# M5_Shield_RS485_V1_1.net
KiCad netlist of a schematic drawn in EAGLE
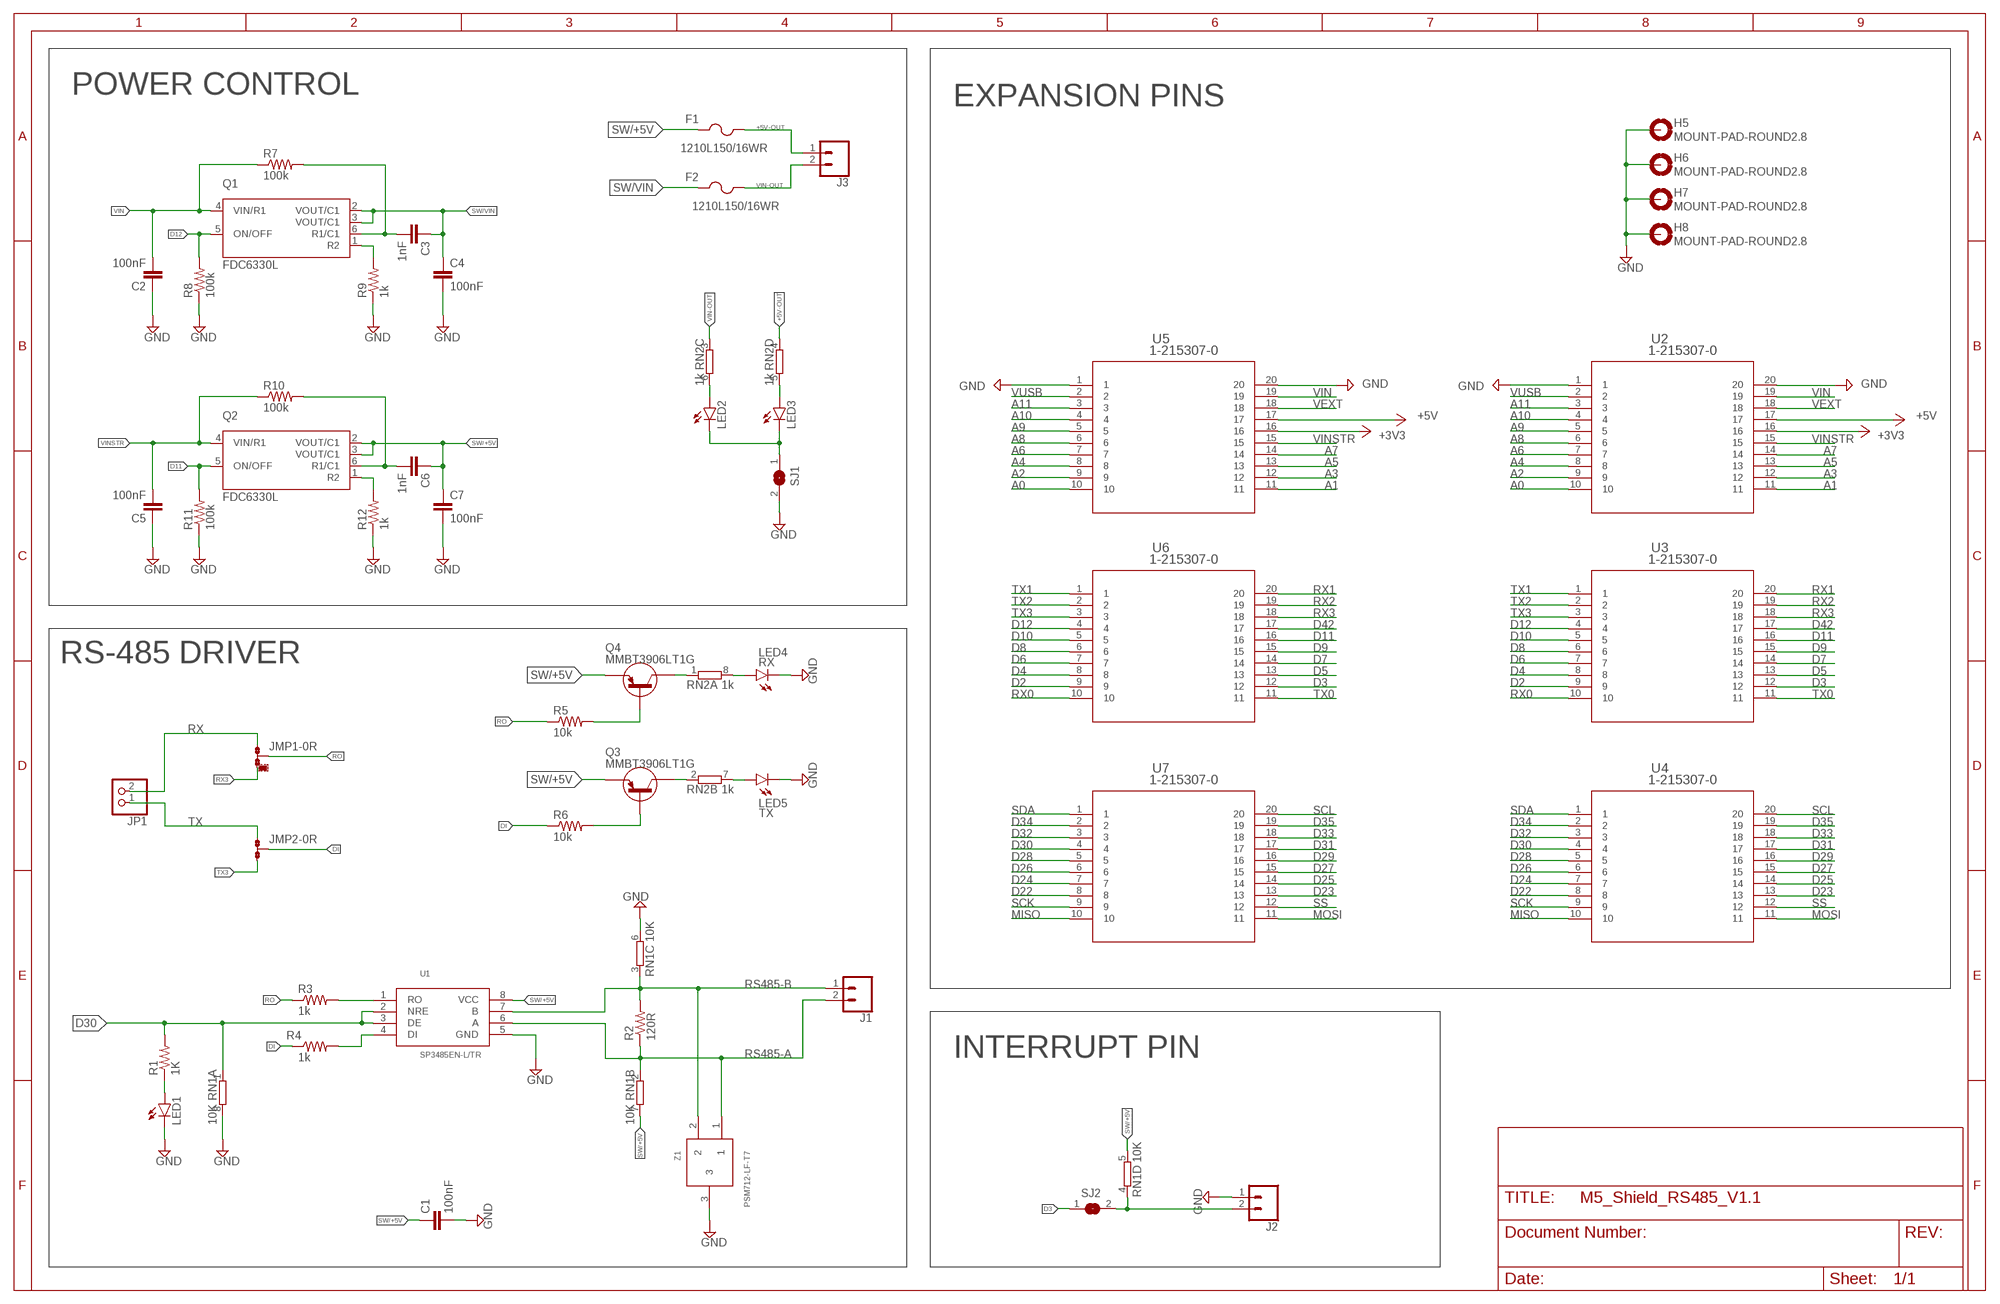
[diagram p0: schematic, sheet 1]

(export (version "E")
  (design (tool "Eeschema 10.0.6"))
  (components
    (comp (ref "C1")
      (value "100nF")
      (footprint "eagle-import:C0603K")
      (libsource (lib "eagle-import") (part "C-EUC0603K"))
    )
    (comp (ref "C2")
      (value "100nF")
      (footprint "eagle-import:C0603")
      (libsource (lib "eagle-import") (part "C-EUC0603"))
    )
    (comp (ref "C3")
      (value "1nF")
      (footprint "eagle-import:C0603")
      (libsource (lib "eagle-import") (part "C-EUC0603"))
    )
    (comp (ref "C4")
      (value "100nF")
      (footprint "eagle-import:C0603")
      (libsource (lib "eagle-import") (part "C-EUC0603"))
    )
    (comp (ref "C5")
      (value "100nF")
      (footprint "eagle-import:C0603")
      (libsource (lib "eagle-import") (part "C-EUC0603"))
    )
    (comp (ref "C6")
      (value "1nF")
      (footprint "eagle-import:C0603")
      (libsource (lib "eagle-import") (part "C-EUC0603"))
    )
    (comp (ref "C7")
      (value "100nF")
      (footprint "eagle-import:C0603")
      (libsource (lib "eagle-import") (part "C-EUC0603"))
    )
    (comp (ref "F1")
      (value "1210L150/16WR")
      (footprint "eagle-import:1210LSERIES")
      (libsource (lib "eagle-import") (part "1210L150/16WR"))
    )
    (comp (ref "F2")
      (value "1210L150/16WR")
      (footprint "eagle-import:1210LSERIES")
      (libsource (lib "eagle-import") (part "1210L150/16WR"))
    )
    (comp (ref "H5")
      (value "MOUNT-PAD-ROUND2.8")
      (footprint "eagle-import:2,8-PAD")
      (libsource (lib "eagle-import") (part "MOUNT-PAD-ROUND2.8"))
    )
    (comp (ref "H6")
      (value "MOUNT-PAD-ROUND2.8")
      (footprint "eagle-import:2,8-PAD")
      (libsource (lib "eagle-import") (part "MOUNT-PAD-ROUND2.8"))
    )
    (comp (ref "H7")
      (value "MOUNT-PAD-ROUND2.8")
      (footprint "eagle-import:2,8-PAD")
      (libsource (lib "eagle-import") (part "MOUNT-PAD-ROUND2.8"))
    )
    (comp (ref "H8")
      (value "MOUNT-PAD-ROUND2.8")
      (footprint "eagle-import:2,8-PAD")
      (libsource (lib "eagle-import") (part "MOUNT-PAD-ROUND2.8"))
    )
    (comp (ref "J1")
      (value "CONN_023.5MM")
      (footprint "eagle-import:SCREWTERMINAL-3.5MM-2")
      (libsource (lib "eagle-import") (part "CONN_023.5MM"))
    )
    (comp (ref "J2")
      (value "CONN_023.5MM")
      (footprint "eagle-import:SCREWTERMINAL-3.5MM-2")
      (libsource (lib "eagle-import") (part "CONN_023.5MM"))
    )
    (comp (ref "J3")
      (value "CONN_023.5MM")
      (footprint "eagle-import:SCREWTERMINAL-3.5MM-2")
      (libsource (lib "eagle-import") (part "CONN_023.5MM"))
    )
    (comp (ref "JMP1")
      (value "0R-JUMPA")
      (footprint "eagle-import:A0R-JMP")
      (libsource (lib "eagle-import") (part "0R-JUMPA"))
    )
    (comp (ref "JMP2")
      (value "0R-JUMPA")
      (footprint "eagle-import:A0R-JMP")
      (libsource (lib "eagle-import") (part "0R-JUMPA"))
    )
    (comp (ref "JP1")
      (value "PINHD-1X2")
      (footprint "eagle-import:1X02")
      (libsource (lib "eagle-import") (part "PINHD-1X2"))
    )
    (comp (ref "LED1")
      (value "LEDCHIPLED_0603")
      (footprint "eagle-import:CHIPLED_0603")
      (libsource (lib "eagle-import") (part "LEDCHIPLED_0603"))
    )
    (comp (ref "LED2")
      (value "LEDCHIP-LED0603")
      (footprint "eagle-import:CHIP-LED0603")
      (libsource (lib "eagle-import") (part "LEDCHIP-LED0603"))
    )
    (comp (ref "LED3")
      (value "LEDCHIP-LED0603")
      (footprint "eagle-import:CHIP-LED0603")
      (libsource (lib "eagle-import") (part "LEDCHIP-LED0603"))
    )
    (comp (ref "LED4")
      (value "RX")
      (footprint "eagle-import:CHIP-LED0603")
      (libsource (lib "eagle-import") (part "LEDCHIP-LED0603"))
    )
    (comp (ref "LED5")
      (value "TX")
      (footprint "eagle-import:CHIP-LED0603")
      (libsource (lib "eagle-import") (part "LEDCHIP-LED0603"))
    )
    (comp (ref "Q1")
      (value "FDC6330L")
      (footprint "eagle-import:SOT95P280X110-6N")
      (fields (field (name "DIGI-KEY_PART_NUMBER") "FDC6330LCT-ND") (field (name "MF") "ON Semiconductor"))
      (libsource (lib "eagle-import") (part "FDC6330L"))
    )
    (comp (ref "Q2")
      (value "FDC6330L")
      (footprint "eagle-import:SOT95P280X110-6N")
      (fields (field (name "DIGI-KEY_PART_NUMBER") "FDC6330LCT-ND") (field (name "MF") "ON Semiconductor"))
      (libsource (lib "eagle-import") (part "FDC6330L"))
    )
    (comp (ref "Q3")
      (value "MMBT3906LT1G")
      (footprint "eagle-import:SOT23")
      (fields (field (name "MF") "ON Semiconductor"))
      (libsource (lib "eagle-import") (part "MMBT3906LT1G"))
    )
    (comp (ref "Q4")
      (value "MMBT3906LT1G")
      (footprint "eagle-import:SOT23")
      (fields (field (name "MF") "ON Semiconductor"))
      (libsource (lib "eagle-import") (part "MMBT3906LT1G"))
    )
    (comp (ref "R1")
      (value "1K")
      (footprint "eagle-import:R0603")
      (libsource (lib "eagle-import") (part "R-US_R0603"))
    )
    (comp (ref "R2")
      (value "120R")
      (footprint "eagle-import:R0603")
      (libsource (lib "eagle-import") (part "R-US_R0603"))
    )
    (comp (ref "R3")
      (value "1k")
      (footprint "eagle-import:R0603")
      (libsource (lib "eagle-import") (part "R-US_R0603"))
    )
    (comp (ref "R4")
      (value "1k")
      (footprint "eagle-import:R0603")
      (libsource (lib "eagle-import") (part "R-US_R0603"))
    )
    (comp (ref "R5")
      (value "10k")
      (footprint "eagle-import:R0603")
      (libsource (lib "eagle-import") (part "R-US_R0603"))
    )
    (comp (ref "R6")
      (value "10k")
      (footprint "eagle-import:R0603")
      (libsource (lib "eagle-import") (part "R-US_R0603"))
    )
    (comp (ref "R7")
      (value "100k")
      (footprint "eagle-import:R0603")
      (libsource (lib "eagle-import") (part "R-US_R0603"))
    )
    (comp (ref "R8")
      (value "100k")
      (footprint "eagle-import:R0603")
      (libsource (lib "eagle-import") (part "R-US_R0603"))
    )
    (comp (ref "R9")
      (value "1k")
      (footprint "eagle-import:R0603")
      (libsource (lib "eagle-import") (part "R-US_R0603"))
    )
    (comp (ref "R10")
      (value "100k")
      (footprint "eagle-import:R0603")
      (libsource (lib "eagle-import") (part "R-US_R0603"))
    )
    (comp (ref "R11")
      (value "100k")
      (footprint "eagle-import:R0603")
      (libsource (lib "eagle-import") (part "R-US_R0603"))
    )
    (comp (ref "R12")
      (value "1k")
      (footprint "eagle-import:R0603")
      (libsource (lib "eagle-import") (part "R-US_R0603"))
    )
    (comp (ref "RN1")
      (value "10K")
      (footprint "eagle-import:0603-ARV")
      (libsource (lib "eagle-import") (part "4R-N0603-ARV"))
    )
    (comp (ref "RN2")
      (value "1k")
      (footprint "eagle-import:0603-ARV")
      (libsource (lib "eagle-import") (part "4R-N0603-ARV"))
    )
    (comp (ref "SJ1") (value "SJ") (footprint "eagle-import:SJ") (libsource (lib "eagle-import") (part "SJ")))
    (comp (ref "SJ2") (value "SJ") (footprint "eagle-import:SJ") (libsource (lib "eagle-import") (part "SJ")))
    (comp (ref "U1")
      (value "SP3485EN-L/TR")
      (footprint "eagle-import:SP3485EN-L_TR")
      (libsource (lib "eagle-import") (part "SP3485EN-L/TR"))
    )
    (comp (ref "U2")
      (value "1-215307-0")
      (footprint "eagle-import:1-215307-0")
      (libsource (lib "eagle-import") (part "1-215307-0"))
    )
    (comp (ref "U3")
      (value "1-215307-0")
      (footprint "eagle-import:1-215307-0")
      (libsource (lib "eagle-import") (part "1-215307-0"))
    )
    (comp (ref "U4")
      (value "1-215307-0")
      (footprint "eagle-import:1-215307-0")
      (libsource (lib "eagle-import") (part "1-215307-0"))
    )
    (comp (ref "U5")
      (value "1-215307-0")
      (footprint "eagle-import:1-215307-0")
      (libsource (lib "eagle-import") (part "1-215307-0"))
    )
    (comp (ref "U6")
      (value "1-215307-0")
      (footprint "eagle-import:1-215307-0")
      (libsource (lib "eagle-import") (part "1-215307-0"))
    )
    (comp (ref "U7")
      (value "1-215307-0")
      (footprint "eagle-import:1-215307-0")
      (libsource (lib "eagle-import") (part "1-215307-0"))
    )
    (comp (ref "Z1")
      (value "PSM712-LF-T7")
      (footprint "eagle-import:SOT23")
      (libsource (lib "eagle-import") (part "PSM712-LF-T7"))
    )
  )
  (nets
    (net (code "1") (name "+3V3") (class "Default")
      (node (ref "U2") (pin "16") (pinfunction "16_16") (pintype "passive"))
      (node (ref "U5") (pin "16") (pinfunction "16_16") (pintype "passive"))
    )
    (net (code "2") (name "+5V") (class "Default")
      (node (ref "U2") (pin "17") (pinfunction "17_17") (pintype "passive"))
      (node (ref "U5") (pin "17") (pinfunction "17_17") (pintype "passive"))
    )
    (net (code "3") (name "+5V-OUT") (class "Default")
      (node (ref "F1") (pin "2") (pinfunction "2_2") (pintype "passive"))
      (node (ref "J3") (pin "1") (pinfunction "1_1") (pintype "passive"))
      (node (ref "RN2") (pin "4") (pinfunction "1_4") (pintype "passive"))
    )
    (net (code "4") (name "/A0") (class "Default")
      (node (ref "U2") (pin "10") (pinfunction "10_10") (pintype "passive"))
      (node (ref "U5") (pin "10") (pinfunction "10_10") (pintype "passive"))
    )
    (net (code "5") (name "/A1") (class "Default")
      (node (ref "U2") (pin "11") (pinfunction "11_11") (pintype "passive"))
      (node (ref "U5") (pin "11") (pinfunction "11_11") (pintype "passive"))
    )
    (net (code "6") (name "/A2") (class "Default")
      (node (ref "U2") (pin "9") (pinfunction "9_9") (pintype "passive"))
      (node (ref "U5") (pin "9") (pinfunction "9_9") (pintype "passive"))
    )
    (net (code "7") (name "/A3") (class "Default")
      (node (ref "U2") (pin "12") (pinfunction "12_12") (pintype "passive"))
      (node (ref "U5") (pin "12") (pinfunction "12_12") (pintype "passive"))
    )
    (net (code "8") (name "/A4") (class "Default")
      (node (ref "U2") (pin "8") (pinfunction "8_8") (pintype "passive"))
      (node (ref "U5") (pin "8") (pinfunction "8_8") (pintype "passive"))
    )
    (net (code "9") (name "/A5") (class "Default")
      (node (ref "U2") (pin "13") (pinfunction "13_13") (pintype "passive"))
      (node (ref "U5") (pin "13") (pinfunction "13_13") (pintype "passive"))
    )
    (net (code "10") (name "/A6") (class "Default")
      (node (ref "U2") (pin "7") (pinfunction "7_7") (pintype "passive"))
      (node (ref "U5") (pin "7") (pinfunction "7_7") (pintype "passive"))
    )
    (net (code "11") (name "/A7") (class "Default")
      (node (ref "U2") (pin "14") (pinfunction "14_14") (pintype "passive"))
      (node (ref "U5") (pin "14") (pinfunction "14_14") (pintype "passive"))
    )
    (net (code "12") (name "/A8") (class "Default")
      (node (ref "U2") (pin "6") (pinfunction "6_6") (pintype "passive"))
      (node (ref "U5") (pin "6") (pinfunction "6_6") (pintype "passive"))
    )
    (net (code "13") (name "/A9") (class "Default")
      (node (ref "U2") (pin "5") (pinfunction "5_5") (pintype "passive"))
      (node (ref "U5") (pin "5") (pinfunction "5_5") (pintype "passive"))
    )
    (net (code "14") (name "/A10") (class "Default")
      (node (ref "U2") (pin "4") (pinfunction "4_4") (pintype "passive"))
      (node (ref "U5") (pin "4") (pinfunction "4_4") (pintype "passive"))
    )
    (net (code "15") (name "/A11") (class "Default")
      (node (ref "U2") (pin "3") (pinfunction "3_3") (pintype "passive"))
      (node (ref "U5") (pin "3") (pinfunction "3_3") (pintype "passive"))
    )
    (net (code "16") (name "/D2") (class "Default")
      (node (ref "U3") (pin "9") (pinfunction "9_9") (pintype "passive"))
      (node (ref "U6") (pin "9") (pinfunction "9_9") (pintype "passive"))
    )
    (net (code "17") (name "/D4") (class "Default")
      (node (ref "U3") (pin "8") (pinfunction "8_8") (pintype "passive"))
      (node (ref "U6") (pin "8") (pinfunction "8_8") (pintype "passive"))
    )
    (net (code "18") (name "/D5") (class "Default")
      (node (ref "U3") (pin "13") (pinfunction "13_13") (pintype "passive"))
      (node (ref "U6") (pin "13") (pinfunction "13_13") (pintype "passive"))
    )
    (net (code "19") (name "/D6") (class "Default")
      (node (ref "U3") (pin "7") (pinfunction "7_7") (pintype "passive"))
      (node (ref "U6") (pin "7") (pinfunction "7_7") (pintype "passive"))
    )
    (net (code "20") (name "/D7") (class "Default")
      (node (ref "U3") (pin "14") (pinfunction "14_14") (pintype "passive"))
      (node (ref "U6") (pin "14") (pinfunction "14_14") (pintype "passive"))
    )
    (net (code "21") (name "/D8") (class "Default")
      (node (ref "U3") (pin "6") (pinfunction "6_6") (pintype "passive"))
      (node (ref "U6") (pin "6") (pinfunction "6_6") (pintype "passive"))
    )
    (net (code "22") (name "/D9") (class "Default")
      (node (ref "U3") (pin "15") (pinfunction "15_15") (pintype "passive"))
      (node (ref "U6") (pin "15") (pinfunction "15_15") (pintype "passive"))
    )
    (net (code "23") (name "/D10") (class "Default")
      (node (ref "U3") (pin "5") (pinfunction "5_5") (pintype "passive"))
      (node (ref "U6") (pin "5") (pinfunction "5_5") (pintype "passive"))
    )
    (net (code "24") (name "/D22") (class "Default")
      (node (ref "U4") (pin "8") (pinfunction "8_8") (pintype "passive"))
      (node (ref "U7") (pin "8") (pinfunction "8_8") (pintype "passive"))
    )
    (net (code "25") (name "/D23") (class "Default")
      (node (ref "U4") (pin "13") (pinfunction "13_13") (pintype "passive"))
      (node (ref "U7") (pin "13") (pinfunction "13_13") (pintype "passive"))
    )
    (net (code "26") (name "/D24") (class "Default")
      (node (ref "U4") (pin "7") (pinfunction "7_7") (pintype "passive"))
      (node (ref "U7") (pin "7") (pinfunction "7_7") (pintype "passive"))
    )
    (net (code "27") (name "/D25") (class "Default")
      (node (ref "U4") (pin "14") (pinfunction "14_14") (pintype "passive"))
      (node (ref "U7") (pin "14") (pinfunction "14_14") (pintype "passive"))
    )
    (net (code "28") (name "/D26") (class "Default")
      (node (ref "U4") (pin "6") (pinfunction "6_6") (pintype "passive"))
      (node (ref "U7") (pin "6") (pinfunction "6_6") (pintype "passive"))
    )
    (net (code "29") (name "/D27") (class "Default")
      (node (ref "U4") (pin "15") (pinfunction "15_15") (pintype "passive"))
      (node (ref "U7") (pin "15") (pinfunction "15_15") (pintype "passive"))
    )
    (net (code "30") (name "/D28") (class "Default")
      (node (ref "U4") (pin "5") (pinfunction "5_5") (pintype "passive"))
      (node (ref "U7") (pin "5") (pinfunction "5_5") (pintype "passive"))
    )
    (net (code "31") (name "/D29") (class "Default")
      (node (ref "U4") (pin "16") (pinfunction "16_16") (pintype "passive"))
      (node (ref "U7") (pin "16") (pinfunction "16_16") (pintype "passive"))
    )
    (net (code "32") (name "/D31") (class "Default")
      (node (ref "U4") (pin "17") (pinfunction "17_17") (pintype "passive"))
      (node (ref "U7") (pin "17") (pinfunction "17_17") (pintype "passive"))
    )
    (net (code "33") (name "/D32") (class "Default")
      (node (ref "U4") (pin "3") (pinfunction "3_3") (pintype "passive"))
      (node (ref "U7") (pin "3") (pinfunction "3_3") (pintype "passive"))
    )
    (net (code "34") (name "/D33") (class "Default")
      (node (ref "U4") (pin "18") (pinfunction "18_18") (pintype "passive"))
      (node (ref "U7") (pin "18") (pinfunction "18_18") (pintype "passive"))
    )
    (net (code "35") (name "/D34") (class "Default")
      (node (ref "U4") (pin "2") (pinfunction "2_2") (pintype "passive"))
      (node (ref "U7") (pin "2") (pinfunction "2_2") (pintype "passive"))
    )
    (net (code "36") (name "/D35") (class "Default")
      (node (ref "U4") (pin "19") (pinfunction "19_19") (pintype "passive"))
      (node (ref "U7") (pin "19") (pinfunction "19_19") (pintype "passive"))
    )
    (net (code "37") (name "/D42") (class "Default")
      (node (ref "U3") (pin "17") (pinfunction "17_17") (pintype "passive"))
      (node (ref "U6") (pin "17") (pinfunction "17_17") (pintype "passive"))
    )
    (net (code "38") (name "/MISO") (class "Default")
      (node (ref "U4") (pin "10") (pinfunction "10_10") (pintype "passive"))
      (node (ref "U7") (pin "10") (pinfunction "10_10") (pintype "passive"))
    )
    (net (code "39") (name "/MOSI") (class "Default")
      (node (ref "U4") (pin "11") (pinfunction "11_11") (pintype "passive"))
      (node (ref "U7") (pin "11") (pinfunction "11_11") (pintype "passive"))
    )
    (net (code "40") (name "/RS485-A") (class "Default")
      (node (ref "J1") (pin "2") (pinfunction "2_2") (pintype "passive"))
      (node (ref "R2") (pin "1") (pinfunction "1_1") (pintype "passive"))
      (node (ref "RN1") (pin "2") (pinfunction "1_2") (pintype "passive"))
      (node (ref "U1") (pin "6") (pinfunction "A_6") (pintype "bidirectional"))
      (node (ref "Z1") (pin "1") (pinfunction "1_1") (pintype "bidirectional"))
    )
    (net (code "41") (name "/RS485-B") (class "Default")
      (node (ref "J1") (pin "1") (pinfunction "1_1") (pintype "passive"))
      (node (ref "R2") (pin "2") (pinfunction "2_2") (pintype "passive"))
      (node (ref "RN1") (pin "3") (pinfunction "1_3") (pintype "passive"))
      (node (ref "U1") (pin "7") (pinfunction "B_7") (pintype "bidirectional"))
      (node (ref "Z1") (pin "2") (pinfunction "2_2") (pintype "bidirectional"))
    )
    (net (code "42") (name "/RX") (class "Default")
      (node (ref "JMP1") (pin "1") (pinfunction "1_1") (pintype "passive"))
      (node (ref "JP1") (pin "2") (pinfunction "2_2") (pintype "passive"))
    )
    (net (code "43") (name "/RX0") (class "Default")
      (node (ref "U3") (pin "10") (pinfunction "10_10") (pintype "passive"))
      (node (ref "U6") (pin "10") (pinfunction "10_10") (pintype "passive"))
    )
    (net (code "44") (name "/RX1") (class "Default")
      (node (ref "U3") (pin "20") (pinfunction "20_20") (pintype "passive"))
      (node (ref "U6") (pin "20") (pinfunction "20_20") (pintype "passive"))
    )
    (net (code "45") (name "/RX2") (class "Default")
      (node (ref "U3") (pin "19") (pinfunction "19_19") (pintype "passive"))
      (node (ref "U6") (pin "19") (pinfunction "19_19") (pintype "passive"))
    )
    (net (code "46") (name "/SCK") (class "Default")
      (node (ref "U4") (pin "9") (pinfunction "9_9") (pintype "passive"))
      (node (ref "U7") (pin "9") (pinfunction "9_9") (pintype "passive"))
    )
    (net (code "47") (name "/SCL") (class "Default")
      (node (ref "U4") (pin "20") (pinfunction "20_20") (pintype "passive"))
      (node (ref "U7") (pin "20") (pinfunction "20_20") (pintype "passive"))
    )
    (net (code "48") (name "/SDA") (class "Default")
      (node (ref "U4") (pin "1") (pinfunction "1_1") (pintype "passive"))
      (node (ref "U7") (pin "1") (pinfunction "1_1") (pintype "passive"))
    )
    (net (code "49") (name "/SS") (class "Default")
      (node (ref "U4") (pin "12") (pinfunction "12_12") (pintype "passive"))
      (node (ref "U7") (pin "12") (pinfunction "12_12") (pintype "passive"))
    )
    (net (code "50") (name "/TX") (class "Default")
      (node (ref "JMP2") (pin "1") (pinfunction "1_1") (pintype "passive"))
      (node (ref "JP1") (pin "1") (pinfunction "1_1") (pintype "passive"))
    )
    (net (code "51") (name "/TX0") (class "Default")
      (node (ref "U3") (pin "11") (pinfunction "11_11") (pintype "passive"))
      (node (ref "U6") (pin "11") (pinfunction "11_11") (pintype "passive"))
    )
    (net (code "52") (name "/TX1") (class "Default")
      (node (ref "U3") (pin "1") (pinfunction "1_1") (pintype "passive"))
      (node (ref "U6") (pin "1") (pinfunction "1_1") (pintype "passive"))
    )
    (net (code "53") (name "/TX2") (class "Default")
      (node (ref "U3") (pin "2") (pinfunction "2_2") (pintype "passive"))
      (node (ref "U6") (pin "2") (pinfunction "2_2") (pintype "passive"))
    )
    (net (code "54") (name "/VEXT") (class "Default")
      (node (ref "U2") (pin "18") (pinfunction "18_18") (pintype "passive"))
      (node (ref "U5") (pin "18") (pinfunction "18_18") (pintype "passive"))
    )
    (net (code "55") (name "/VUSB") (class "Default")
      (node (ref "U2") (pin "2") (pinfunction "2_2") (pintype "passive"))
      (node (ref "U5") (pin "2") (pinfunction "2_2") (pintype "passive"))
    )
    (net (code "56") (name "D3") (class "Default")
      (node (ref "SJ2") (pin "1") (pinfunction "1_1") (pintype "passive"))
      (node (ref "U3") (pin "12") (pinfunction "12_12") (pintype "passive"))
      (node (ref "U6") (pin "12") (pinfunction "12_12") (pintype "passive"))
    )
    (net (code "57") (name "D11") (class "Default")
      (node (ref "Q2") (pin "5") (pinfunction "ON/OFF_5") (pintype "input"))
      (node (ref "R11") (pin "2") (pinfunction "2_2") (pintype "passive"))
      (node (ref "U3") (pin "16") (pinfunction "16_16") (pintype "passive"))
      (node (ref "U6") (pin "16") (pinfunction "16_16") (pintype "passive"))
    )
    (net (code "58") (name "D12") (class "Default")
      (node (ref "Q1") (pin "5") (pinfunction "ON/OFF_5") (pintype "input"))
      (node (ref "R8") (pin "2") (pinfunction "2_2") (pintype "passive"))
      (node (ref "U3") (pin "4") (pinfunction "4_4") (pintype "passive"))
      (node (ref "U6") (pin "4") (pinfunction "4_4") (pintype "passive"))
    )
    (net (code "59") (name "D30") (class "Default")
      (node (ref "R1") (pin "2") (pinfunction "2_2") (pintype "passive"))
      (node (ref "RN1") (pin "1") (pinfunction "1_1") (pintype "passive"))
      (node (ref "U1") (pin "2") (pinfunction "NRE_2") (pintype "bidirectional"))
      (node (ref "U1") (pin "3") (pinfunction "DE_3") (pintype "bidirectional"))
      (node (ref "U4") (pin "4") (pinfunction "4_4") (pintype "passive"))
      (node (ref "U7") (pin "4") (pinfunction "4_4") (pintype "passive"))
    )
    (net (code "60") (name "DI") (class "Default")
      (node (ref "JMP2") (pin "2") (pinfunction "2_2") (pintype "passive"))
      (node (ref "R4") (pin "1") (pinfunction "1_1") (pintype "passive"))
      (node (ref "R6") (pin "1") (pinfunction "1_1") (pintype "passive"))
    )
    (net (code "61") (name "GND") (class "Default")
      (node (ref "C1") (pin "2") (pinfunction "2_2") (pintype "passive"))
      (node (ref "C2") (pin "1") (pinfunction "1_1") (pintype "passive"))
      (node (ref "C4") (pin "2") (pinfunction "2_2") (pintype "passive"))
      (node (ref "C5") (pin "1") (pinfunction "1_1") (pintype "passive"))
      (node (ref "C7") (pin "2") (pinfunction "2_2") (pintype "passive"))
      (node (ref "H5") (pin "B2,8") (pinfunction "MOUNT_B2,8") (pintype "passive"))
      (node (ref "H6") (pin "B2,8") (pinfunction "MOUNT_B2,8") (pintype "passive"))
      (node (ref "H7") (pin "B2,8") (pinfunction "MOUNT_B2,8") (pintype "passive"))
      (node (ref "H8") (pin "B2,8") (pinfunction "MOUNT_B2,8") (pintype "passive"))
      (node (ref "J2") (pin "1") (pinfunction "1_1") (pintype "passive"))
      (node (ref "LED1") (pin "C") (pinfunction "C_C") (pintype "passive"))
      (node (ref "LED4") (pin "C") (pinfunction "C_C") (pintype "passive"))
      (node (ref "LED5") (pin "C") (pinfunction "C_C") (pintype "passive"))
      (node (ref "R11") (pin "1") (pinfunction "1_1") (pintype "passive"))
      (node (ref "R12") (pin "1") (pinfunction "1_1") (pintype "passive"))
      (node (ref "R8") (pin "1") (pinfunction "1_1") (pintype "passive"))
      (node (ref "R9") (pin "1") (pinfunction "1_1") (pintype "passive"))
      (node (ref "RN1") (pin "6") (pinfunction "2_6") (pintype "passive"))
      (node (ref "RN1") (pin "8") (pinfunction "2_8") (pintype "passive"))
      (node (ref "SJ1") (pin "2") (pinfunction "2_2") (pintype "passive"))
      (node (ref "U1") (pin "5") (pinfunction "GND_5") (pintype "bidirectional"))
      (node (ref "U2") (pin "1") (pinfunction "1_1") (pintype "passive"))
      (node (ref "U2") (pin "20") (pinfunction "20_20") (pintype "passive"))
      (node (ref "U5") (pin "1") (pinfunction "1_1") (pintype "passive"))
      (node (ref "U5") (pin "20") (pinfunction "20_20") (pintype "passive"))
      (node (ref "Z1") (pin "3") (pinfunction "3_3") (pintype "bidirectional"))
    )
    (net (code "62") (name "Net-(LED1-PadA)") (class "Default")
      (node (ref "LED1") (pin "A") (pinfunction "A_A") (pintype "passive"))
      (node (ref "R1") (pin "1") (pinfunction "1_1") (pintype "passive"))
    )
    (net (code "63") (name "Net-(LED2-PadC)") (class "Default")
      (node (ref "LED2") (pin "C") (pinfunction "C_C") (pintype "passive"))
      (node (ref "LED3") (pin "C") (pinfunction "C_C") (pintype "passive"))
      (node (ref "SJ1") (pin "1") (pinfunction "1_1") (pintype "passive"))
    )
    (net (code "64") (name "Net-(Q1-R1{slash}C1)") (class "Default")
      (node (ref "C3") (pin "2") (pinfunction "2_2") (pintype "passive"))
      (node (ref "Q1") (pin "6") (pinfunction "R1/C1_6") (pintype "passive"))
      (node (ref "R7") (pin "2") (pinfunction "2_2") (pintype "passive"))
    )
    (net (code "65") (name "Net-(Q1-R2)") (class "Default")
      (node (ref "Q1") (pin "1") (pinfunction "R2_1") (pintype "passive"))
      (node (ref "R9") (pin "2") (pinfunction "2_2") (pintype "passive"))
    )
    (net (code "66") (name "Net-(Q2-R1{slash}C1)") (class "Default")
      (node (ref "C6") (pin "2") (pinfunction "2_2") (pintype "passive"))
      (node (ref "Q2") (pin "6") (pinfunction "R1/C1_6") (pintype "passive"))
      (node (ref "R10") (pin "2") (pinfunction "2_2") (pintype "passive"))
    )
    (net (code "67") (name "Net-(Q2-R2)") (class "Default")
      (node (ref "Q2") (pin "1") (pinfunction "R2_1") (pintype "passive"))
      (node (ref "R12") (pin "2") (pinfunction "2_2") (pintype "passive"))
    )
    (net (code "68") (name "Net-(Q3-B)") (class "Default")
      (node (ref "Q3") (pin "1") (pinfunction "B_1") (pintype "passive"))
      (node (ref "R6") (pin "2") (pinfunction "2_2") (pintype "passive"))
    )
    (net (code "69") (name "Net-(Q3-C)") (class "Default")
      (node (ref "Q3") (pin "3") (pinfunction "C_3") (pintype "passive"))
      (node (ref "RN2") (pin "2") (pinfunction "1_2") (pintype "passive"))
    )
    (net (code "70") (name "Net-(Q4-B)") (class "Default")
      (node (ref "Q4") (pin "1") (pinfunction "B_1") (pintype "passive"))
      (node (ref "R5") (pin "2") (pinfunction "2_2") (pintype "passive"))
    )
    (net (code "71") (name "Net-(Q4-C)") (class "Default")
      (node (ref "Q4") (pin "3") (pinfunction "C_3") (pintype "passive"))
      (node (ref "RN2") (pin "1") (pinfunction "1_1") (pintype "passive"))
    )
    (net (code "72") (name "Net-(RN1D-1)") (class "Default")
      (node (ref "J2") (pin "2") (pinfunction "2_2") (pintype "passive"))
      (node (ref "RN1") (pin "4") (pinfunction "1_4") (pintype "passive"))
      (node (ref "SJ2") (pin "2") (pinfunction "2_2") (pintype "passive"))
    )
    (net (code "73") (name "Net-(RN2A-2)") (class "Default")
      (node (ref "LED4") (pin "A") (pinfunction "A_A") (pintype "passive"))
      (node (ref "RN2") (pin "8") (pinfunction "2_8") (pintype "passive"))
    )
    (net (code "74") (name "Net-(RN2B-2)") (class "Default")
      (node (ref "LED5") (pin "A") (pinfunction "A_A") (pintype "passive"))
      (node (ref "RN2") (pin "7") (pinfunction "2_7") (pintype "passive"))
    )
    (net (code "75") (name "Net-(RN2C-2)") (class "Default")
      (node (ref "LED2") (pin "A") (pinfunction "A_A") (pintype "passive"))
      (node (ref "RN2") (pin "6") (pinfunction "2_6") (pintype "passive"))
    )
    (net (code "76") (name "Net-(RN2D-2)") (class "Default")
      (node (ref "LED3") (pin "A") (pinfunction "A_A") (pintype "passive"))
      (node (ref "RN2") (pin "5") (pinfunction "2_5") (pintype "passive"))
    )
    (net (code "77") (name "Net-(U1-DI)") (class "Default")
      (node (ref "R4") (pin "2") (pinfunction "2_2") (pintype "passive"))
      (node (ref "U1") (pin "4") (pinfunction "DI_4") (pintype "bidirectional"))
    )
    (net (code "78") (name "Net-(U1-RO)") (class "Default")
      (node (ref "R3") (pin "2") (pinfunction "2_2") (pintype "passive"))
      (node (ref "U1") (pin "1") (pinfunction "RO_1") (pintype "bidirectional"))
    )
    (net (code "79") (name "RO") (class "Default")
      (node (ref "JMP1") (pin "2") (pinfunction "2_2") (pintype "passive"))
      (node (ref "R3") (pin "1") (pinfunction "1_1") (pintype "passive"))
      (node (ref "R5") (pin "1") (pinfunction "1_1") (pintype "passive"))
    )
    (net (code "80") (name "RX3") (class "Default")
      (node (ref "JMP1") (pin "3") (pinfunction "3_3") (pintype "passive"))
      (node (ref "U3") (pin "18") (pinfunction "18_18") (pintype "passive"))
      (node (ref "U6") (pin "18") (pinfunction "18_18") (pintype "passive"))
    )
    (net (code "81") (name "SW{slash}+5V") (class "Default")
      (node (ref "C1") (pin "1") (pinfunction "1_1") (pintype "passive"))
      (node (ref "C6") (pin "1") (pinfunction "1_1") (pintype "passive"))
      (node (ref "C7") (pin "1") (pinfunction "1_1") (pintype "passive"))
      (node (ref "F1") (pin "1") (pinfunction "1_1") (pintype "passive"))
      (node (ref "Q2") (pin "2") (pinfunction "VOUT/C1_2") (pintype "output"))
      (node (ref "Q2") (pin "3") (pinfunction "VOUT/C1_3") (pintype "output"))
      (node (ref "Q3") (pin "2") (pinfunction "E_2") (pintype "passive"))
      (node (ref "Q4") (pin "2") (pinfunction "E_2") (pintype "passive"))
      (node (ref "RN1") (pin "5") (pinfunction "2_5") (pintype "passive"))
      (node (ref "RN1") (pin "7") (pinfunction "2_7") (pintype "passive"))
      (node (ref "U1") (pin "8") (pinfunction "VCC_8") (pintype "bidirectional"))
    )
    (net (code "82") (name "SW{slash}VIN") (class "Default")
      (node (ref "C3") (pin "1") (pinfunction "1_1") (pintype "passive"))
      (node (ref "C4") (pin "1") (pinfunction "1_1") (pintype "passive"))
      (node (ref "F2") (pin "1") (pinfunction "1_1") (pintype "passive"))
      (node (ref "Q1") (pin "2") (pinfunction "VOUT/C1_2") (pintype "output"))
      (node (ref "Q1") (pin "3") (pinfunction "VOUT/C1_3") (pintype "output"))
    )
    (net (code "83") (name "TX3") (class "Default")
      (node (ref "JMP2") (pin "3") (pinfunction "3_3") (pintype "passive"))
      (node (ref "U3") (pin "3") (pinfunction "3_3") (pintype "passive"))
      (node (ref "U6") (pin "3") (pinfunction "3_3") (pintype "passive"))
    )
    (net (code "84") (name "VIN") (class "Default")
      (node (ref "C2") (pin "2") (pinfunction "2_2") (pintype "passive"))
      (node (ref "Q1") (pin "4") (pinfunction "VIN/R1_4") (pintype "input"))
      (node (ref "R7") (pin "1") (pinfunction "1_1") (pintype "passive"))
      (node (ref "U2") (pin "19") (pinfunction "19_19") (pintype "passive"))
      (node (ref "U5") (pin "19") (pinfunction "19_19") (pintype "passive"))
    )
    (net (code "85") (name "VIN-OUT") (class "Default")
      (node (ref "F2") (pin "2") (pinfunction "2_2") (pintype "passive"))
      (node (ref "J3") (pin "2") (pinfunction "2_2") (pintype "passive"))
      (node (ref "RN2") (pin "3") (pinfunction "1_3") (pintype "passive"))
    )
    (net (code "86") (name "VINSTR") (class "Default")
      (node (ref "C5") (pin "2") (pinfunction "2_2") (pintype "passive"))
      (node (ref "Q2") (pin "4") (pinfunction "VIN/R1_4") (pintype "input"))
      (node (ref "R10") (pin "1") (pinfunction "1_1") (pintype "passive"))
      (node (ref "U2") (pin "15") (pinfunction "15_15") (pintype "passive"))
      (node (ref "U5") (pin "15") (pinfunction "15_15") (pintype "passive"))
    )
  )
)
